# l5.net
KiCad netlist of a schematic drawn in Altium Designer
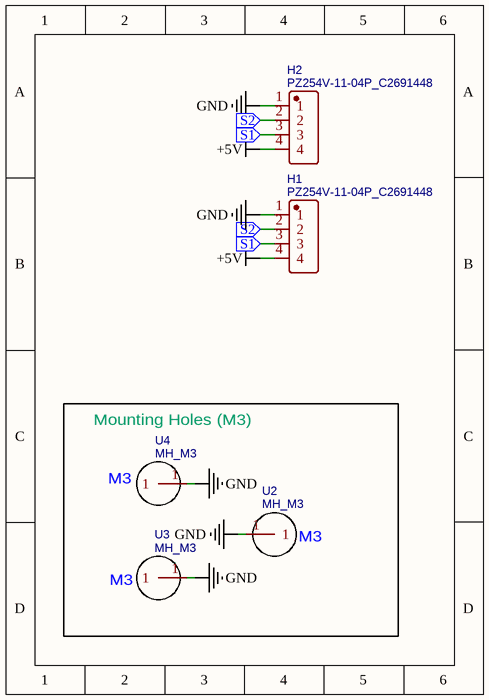
[diagram p0: l5.schdoc]

(export (version "E")
  (design (tool "Eeschema 10.0.6"))
  (components
    (comp (ref "H1")
      (value "PZ254V-11-04P_C2691448")
      (fields
        (field (name "MANUFACTURER") "XFCN(兴飞)")
        (field (name "MANUFACTURER PART") "PZ254V-11-04P")
        (field (name "CONTRIBUTOR") "LCSC")
      )
      (libsource (lib "altium-import") (part "root_0_PZ254V-11-04P_C2691448_"))
    )
    (comp (ref "H2")
      (value "PZ254V-11-04P_C2691448")
      (fields
        (field (name "MANUFACTURER") "XFCN(兴飞)")
        (field (name "MANUFACTURER PART") "PZ254V-11-04P")
        (field (name "CONTRIBUTOR") "LCSC")
      )
      (libsource (lib "altium-import") (part "root_0_PZ254V-11-04P_C2691448_"))
    )
    (comp (ref "U2")
      (value "MH_M3")
      (fields (field (name "CONTRIBUTOR") "js314dev"))
      (libsource (lib "altium-import") (part "root_2_MH_M3_"))
    )
    (comp (ref "U3")
      (value "MH_M3")
      (fields (field (name "CONTRIBUTOR") "js314dev"))
      (libsource (lib "altium-import") (part "root_0_MH_M3_"))
    )
    (comp (ref "U4")
      (value "MH_M3")
      (fields (field (name "CONTRIBUTOR") "js314dev"))
      (libsource (lib "altium-import") (part "root_0_MH_M3_"))
    )
  )
  (nets
    (net (code "1") (name "+5V") (class "Default")
      (node (ref "H1") (pin "4") (pinfunction "4_4") (pintype "passive"))
      (node (ref "H2") (pin "4") (pinfunction "4_4") (pintype "passive"))
    )
    (net (code "2") (name "/S1") (class "Default")
      (node (ref "H1") (pin "3") (pinfunction "3_3") (pintype "passive"))
      (node (ref "H2") (pin "3") (pinfunction "3_3") (pintype "passive"))
    )
    (net (code "3") (name "/S2") (class "Default")
      (node (ref "H1") (pin "2") (pinfunction "2_2") (pintype "passive"))
      (node (ref "H2") (pin "2") (pinfunction "2_2") (pintype "passive"))
    )
    (net (code "4") (name "GND") (class "Default")
      (node (ref "H1") (pin "1") (pinfunction "1_1") (pintype "passive"))
      (node (ref "H2") (pin "1") (pinfunction "1_1") (pintype "passive"))
      (node (ref "U2") (pin "1") (pinfunction "1_1") (pintype "passive"))
      (node (ref "U3") (pin "1") (pinfunction "1_1") (pintype "passive"))
      (node (ref "U4") (pin "1") (pinfunction "1_1") (pintype "passive"))
    )
  )
)
